# Amplifier.net
KiCad netlist of a schematic drawn in EAGLE
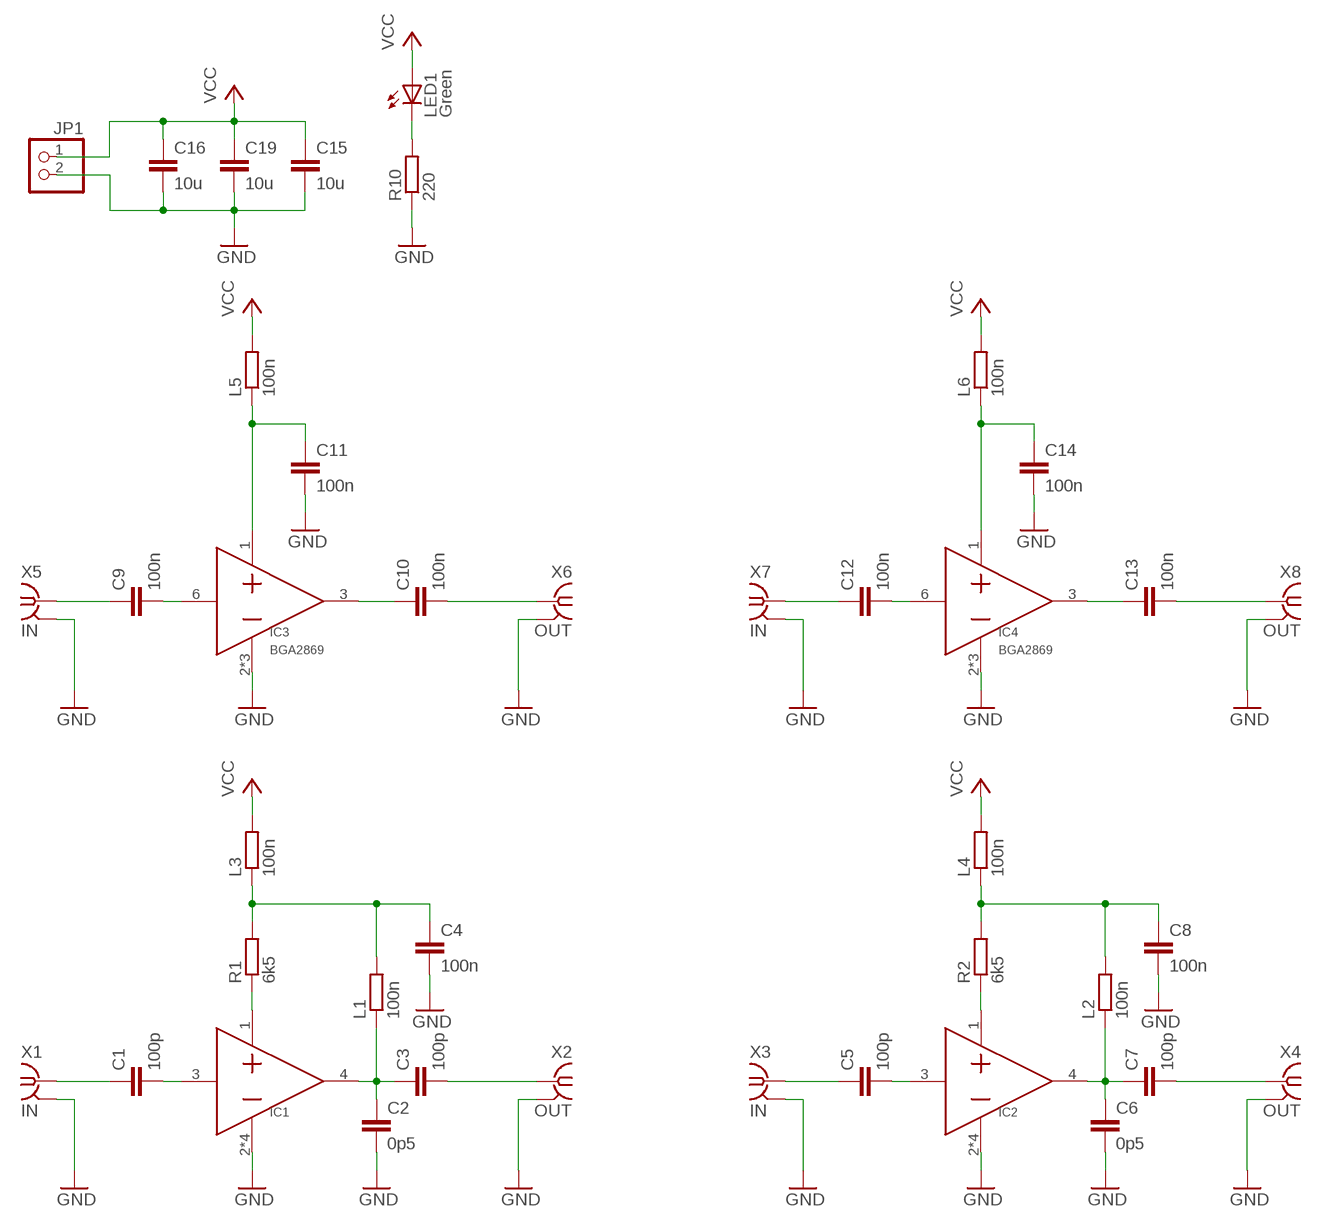
[diagram p0: schematic, sheet 1]

(export (version "E")
  (design (tool "Eeschema 10.0.6"))
  (components
    (comp (ref "C1")
      (value "100p")
      (footprint "eagle-import:C0603")
      (libsource (lib "eagle-import") (part "C-EUC0603"))
    )
    (comp (ref "C2")
      (value "0p5")
      (footprint "eagle-import:C0603")
      (libsource (lib "eagle-import") (part "C-EUC0603"))
    )
    (comp (ref "C3")
      (value "100p")
      (footprint "eagle-import:C0603")
      (libsource (lib "eagle-import") (part "C-EUC0603"))
    )
    (comp (ref "C4")
      (value "100n")
      (footprint "eagle-import:C0603")
      (libsource (lib "eagle-import") (part "C-EUC0603"))
    )
    (comp (ref "C5")
      (value "100p")
      (footprint "eagle-import:C0603")
      (libsource (lib "eagle-import") (part "C-EUC0603"))
    )
    (comp (ref "C6")
      (value "0p5")
      (footprint "eagle-import:C0603")
      (libsource (lib "eagle-import") (part "C-EUC0603"))
    )
    (comp (ref "C7")
      (value "100p")
      (footprint "eagle-import:C0603")
      (libsource (lib "eagle-import") (part "C-EUC0603"))
    )
    (comp (ref "C8")
      (value "100n")
      (footprint "eagle-import:C0603")
      (libsource (lib "eagle-import") (part "C-EUC0603"))
    )
    (comp (ref "C9")
      (value "100n")
      (footprint "eagle-import:C0603")
      (libsource (lib "eagle-import") (part "C-EUC0603"))
    )
    (comp (ref "C10")
      (value "100n")
      (footprint "eagle-import:C0603")
      (libsource (lib "eagle-import") (part "C-EUC0603"))
    )
    (comp (ref "C11")
      (value "100n")
      (footprint "eagle-import:C0603")
      (libsource (lib "eagle-import") (part "C-EUC0603"))
    )
    (comp (ref "C12")
      (value "100n")
      (footprint "eagle-import:C0603")
      (libsource (lib "eagle-import") (part "C-EUC0603"))
    )
    (comp (ref "C13")
      (value "100n")
      (footprint "eagle-import:C0603")
      (libsource (lib "eagle-import") (part "C-EUC0603"))
    )
    (comp (ref "C14")
      (value "100n")
      (footprint "eagle-import:C0603")
      (libsource (lib "eagle-import") (part "C-EUC0603"))
    )
    (comp (ref "C15")
      (value "10u")
      (footprint "eagle-import:C1206")
      (libsource (lib "eagle-import") (part "C-EUC1206"))
    )
    (comp (ref "C16")
      (value "10u")
      (footprint "eagle-import:C1206")
      (libsource (lib "eagle-import") (part "C-EUC1206"))
    )
    (comp (ref "C19")
      (value "10u")
      (footprint "eagle-import:C1206")
      (libsource (lib "eagle-import") (part "C-EUC1206"))
    )
    (comp (ref "IC1")
      (value "GRF4002")
      (footprint "eagle-import:SON50P150X150X45-7T60X110")
      (libsource (lib "eagle-import") (part "GRF4002"))
    )
    (comp (ref "IC2")
      (value "GRF4002")
      (footprint "eagle-import:SON50P150X150X45-7T60X110")
      (libsource (lib "eagle-import") (part "GRF4002"))
    )
    (comp (ref "IC3")
      (value "BGA2869")
      (footprint "eagle-import:SOT363")
      (libsource (lib "eagle-import") (part "BGA2869"))
    )
    (comp (ref "IC4")
      (value "BGA2869")
      (footprint "eagle-import:SOT363")
      (libsource (lib "eagle-import") (part "BGA2869"))
    )
    (comp (ref "JP1")
      (value "PINHD-1X2/90")
      (footprint "eagle-import:1X02_90")
      (libsource (lib "eagle-import") (part "PINHD-1X2/90"))
    )
    (comp (ref "L1")
      (value "100n")
      (footprint "eagle-import:R0603")
      (libsource (lib "eagle-import") (part "R-EU_R0603"))
    )
    (comp (ref "L2")
      (value "100n")
      (footprint "eagle-import:R0603")
      (libsource (lib "eagle-import") (part "R-EU_R0603"))
    )
    (comp (ref "L3")
      (value "100n")
      (footprint "eagle-import:R0603")
      (libsource (lib "eagle-import") (part "R-EU_R0603"))
    )
    (comp (ref "L4")
      (value "100n")
      (footprint "eagle-import:R0603")
      (libsource (lib "eagle-import") (part "R-EU_R0603"))
    )
    (comp (ref "L5")
      (value "100n")
      (footprint "eagle-import:R0603")
      (libsource (lib "eagle-import") (part "R-EU_R0603"))
    )
    (comp (ref "L6")
      (value "100n")
      (footprint "eagle-import:R0603")
      (libsource (lib "eagle-import") (part "R-EU_R0603"))
    )
    (comp (ref "LED1")
      (value "Green")
      (footprint "eagle-import:LED_SML0603")
      (libsource (lib "eagle-import") (part "LED_ESML0603"))
    )
    (comp (ref "R1")
      (value "6k5")
      (footprint "eagle-import:R0603")
      (libsource (lib "eagle-import") (part "R-EU_R0603"))
    )
    (comp (ref "R2")
      (value "6k5")
      (footprint "eagle-import:R0603")
      (libsource (lib "eagle-import") (part "R-EU_R0603"))
    )
    (comp (ref "R10")
      (value "220")
      (footprint "eagle-import:R0603")
      (libsource (lib "eagle-import") (part "R-EU_R0603"))
    )
    (comp (ref "X1")
      (value "IN")
      (footprint "eagle-import:J502-ND-142-0711-821_826")
      (libsource (lib "eagle-import") (part "SMA_CONNECTOR"))
    )
    (comp (ref "X2")
      (value "OUT")
      (footprint "eagle-import:J502-ND-142-0711-821_826")
      (libsource (lib "eagle-import") (part "SMA_CONNECTOR"))
    )
    (comp (ref "X3")
      (value "IN")
      (footprint "eagle-import:J502-ND-142-0711-821_826")
      (libsource (lib "eagle-import") (part "SMA_CONNECTOR"))
    )
    (comp (ref "X4")
      (value "OUT")
      (footprint "eagle-import:J502-ND-142-0711-821_826")
      (libsource (lib "eagle-import") (part "SMA_CONNECTOR"))
    )
    (comp (ref "X5")
      (value "IN")
      (footprint "eagle-import:J502-ND-142-0711-821_826")
      (libsource (lib "eagle-import") (part "SMA_CONNECTOR"))
    )
    (comp (ref "X6")
      (value "OUT")
      (footprint "eagle-import:J502-ND-142-0711-821_826")
      (libsource (lib "eagle-import") (part "SMA_CONNECTOR"))
    )
    (comp (ref "X7")
      (value "IN")
      (footprint "eagle-import:J502-ND-142-0711-821_826")
      (libsource (lib "eagle-import") (part "SMA_CONNECTOR"))
    )
    (comp (ref "X8")
      (value "OUT")
      (footprint "eagle-import:J502-ND-142-0711-821_826")
      (libsource (lib "eagle-import") (part "SMA_CONNECTOR"))
    )
  )
  (nets
    (net (code "1") (name "GND") (class "Default")
      (node (ref "C11") (pin "2") (pinfunction "2_2") (pintype "passive"))
      (node (ref "C14") (pin "2") (pinfunction "2_2") (pintype "passive"))
      (node (ref "C15") (pin "2") (pinfunction "2_2") (pintype "passive"))
      (node (ref "C16") (pin "2") (pinfunction "2_2") (pintype "passive"))
      (node (ref "C19") (pin "2") (pinfunction "2_2") (pintype "passive"))
      (node (ref "C2") (pin "2") (pinfunction "2_2") (pintype "passive"))
      (node (ref "C4") (pin "2") (pinfunction "2_2") (pintype "passive"))
      (node (ref "C6") (pin "2") (pinfunction "2_2") (pintype "passive"))
      (node (ref "C8") (pin "2") (pinfunction "2_2") (pintype "passive"))
      (node (ref "IC1") (pin "2") (pinfunction "GND_2") (pintype "bidirectional"))
      (node (ref "IC1") (pin "5") (pinfunction "GND_5") (pintype "bidirectional"))
      (node (ref "IC1") (pin "6") (pinfunction "GND_6") (pintype "bidirectional"))
      (node (ref "IC1") (pin "7") (pinfunction "GND_7") (pintype "bidirectional"))
      (node (ref "IC2") (pin "2") (pinfunction "GND_2") (pintype "bidirectional"))
      (node (ref "IC2") (pin "5") (pinfunction "GND_5") (pintype "bidirectional"))
      (node (ref "IC2") (pin "6") (pinfunction "GND_6") (pintype "bidirectional"))
      (node (ref "IC2") (pin "7") (pinfunction "GND_7") (pintype "bidirectional"))
      (node (ref "IC3") (pin "2") (pinfunction "GND_2") (pintype "bidirectional"))
      (node (ref "IC3") (pin "4") (pinfunction "GND_4") (pintype "bidirectional"))
      (node (ref "IC3") (pin "5") (pinfunction "GND_5") (pintype "bidirectional"))
      (node (ref "IC4") (pin "2") (pinfunction "GND_2") (pintype "bidirectional"))
      (node (ref "IC4") (pin "4") (pinfunction "GND_4") (pintype "bidirectional"))
      (node (ref "IC4") (pin "5") (pinfunction "GND_5") (pintype "bidirectional"))
      (node (ref "JP1") (pin "2") (pinfunction "2_2") (pintype "passive"))
      (node (ref "R10") (pin "1") (pinfunction "1_1") (pintype "passive"))
      (node (ref "X1") (pin "G@1") (pinfunction "2_G@1") (pintype "passive"))
      (node (ref "X1") (pin "G@2") (pinfunction "2_G@2") (pintype "passive"))
      (node (ref "X1") (pin "G@3") (pinfunction "2_G@3") (pintype "passive"))
      (node (ref "X1") (pin "G@4") (pinfunction "2_G@4") (pintype "passive"))
      (node (ref "X2") (pin "G@1") (pinfunction "2_G@1") (pintype "passive"))
      (node (ref "X2") (pin "G@2") (pinfunction "2_G@2") (pintype "passive"))
      (node (ref "X2") (pin "G@3") (pinfunction "2_G@3") (pintype "passive"))
      (node (ref "X2") (pin "G@4") (pinfunction "2_G@4") (pintype "passive"))
      (node (ref "X3") (pin "G@1") (pinfunction "2_G@1") (pintype "passive"))
      (node (ref "X3") (pin "G@2") (pinfunction "2_G@2") (pintype "passive"))
      (node (ref "X3") (pin "G@3") (pinfunction "2_G@3") (pintype "passive"))
      (node (ref "X3") (pin "G@4") (pinfunction "2_G@4") (pintype "passive"))
      (node (ref "X4") (pin "G@1") (pinfunction "2_G@1") (pintype "passive"))
      (node (ref "X4") (pin "G@2") (pinfunction "2_G@2") (pintype "passive"))
      (node (ref "X4") (pin "G@3") (pinfunction "2_G@3") (pintype "passive"))
      (node (ref "X4") (pin "G@4") (pinfunction "2_G@4") (pintype "passive"))
      (node (ref "X5") (pin "G@1") (pinfunction "2_G@1") (pintype "passive"))
      (node (ref "X5") (pin "G@2") (pinfunction "2_G@2") (pintype "passive"))
      (node (ref "X5") (pin "G@3") (pinfunction "2_G@3") (pintype "passive"))
      (node (ref "X5") (pin "G@4") (pinfunction "2_G@4") (pintype "passive"))
      (node (ref "X6") (pin "G@1") (pinfunction "2_G@1") (pintype "passive"))
      (node (ref "X6") (pin "G@2") (pinfunction "2_G@2") (pintype "passive"))
      (node (ref "X6") (pin "G@3") (pinfunction "2_G@3") (pintype "passive"))
      (node (ref "X6") (pin "G@4") (pinfunction "2_G@4") (pintype "passive"))
      (node (ref "X7") (pin "G@1") (pinfunction "2_G@1") (pintype "passive"))
      (node (ref "X7") (pin "G@2") (pinfunction "2_G@2") (pintype "passive"))
      (node (ref "X7") (pin "G@3") (pinfunction "2_G@3") (pintype "passive"))
      (node (ref "X7") (pin "G@4") (pinfunction "2_G@4") (pintype "passive"))
      (node (ref "X8") (pin "G@1") (pinfunction "2_G@1") (pintype "passive"))
      (node (ref "X8") (pin "G@2") (pinfunction "2_G@2") (pintype "passive"))
      (node (ref "X8") (pin "G@3") (pinfunction "2_G@3") (pintype "passive"))
      (node (ref "X8") (pin "G@4") (pinfunction "2_G@4") (pintype "passive"))
    )
    (net (code "2") (name "Net-(C1-Pad1)") (class "Default")
      (node (ref "C1") (pin "1") (pinfunction "1_1") (pintype "passive"))
      (node (ref "X1") (pin "1") (pinfunction "1_1") (pintype "passive"))
    )
    (net (code "3") (name "Net-(C3-Pad2)") (class "Default")
      (node (ref "C3") (pin "2") (pinfunction "2_2") (pintype "passive"))
      (node (ref "X2") (pin "1") (pinfunction "1_1") (pintype "passive"))
    )
    (net (code "4") (name "Net-(C4-Pad1)") (class "Default")
      (node (ref "C4") (pin "1") (pinfunction "1_1") (pintype "passive"))
      (node (ref "L1") (pin "2") (pinfunction "2_2") (pintype "passive"))
      (node (ref "L3") (pin "1") (pinfunction "1_1") (pintype "passive"))
      (node (ref "R1") (pin "2") (pinfunction "2_2") (pintype "passive"))
    )
    (net (code "5") (name "Net-(C5-Pad1)") (class "Default")
      (node (ref "C5") (pin "1") (pinfunction "1_1") (pintype "passive"))
      (node (ref "X3") (pin "1") (pinfunction "1_1") (pintype "passive"))
    )
    (net (code "6") (name "Net-(C7-Pad2)") (class "Default")
      (node (ref "C7") (pin "2") (pinfunction "2_2") (pintype "passive"))
      (node (ref "X4") (pin "1") (pinfunction "1_1") (pintype "passive"))
    )
    (net (code "7") (name "Net-(C8-Pad1)") (class "Default")
      (node (ref "C8") (pin "1") (pinfunction "1_1") (pintype "passive"))
      (node (ref "L2") (pin "2") (pinfunction "2_2") (pintype "passive"))
      (node (ref "L4") (pin "1") (pinfunction "1_1") (pintype "passive"))
      (node (ref "R2") (pin "2") (pinfunction "2_2") (pintype "passive"))
    )
    (net (code "8") (name "Net-(C9-Pad1)") (class "Default")
      (node (ref "C9") (pin "1") (pinfunction "1_1") (pintype "passive"))
      (node (ref "X5") (pin "1") (pinfunction "1_1") (pintype "passive"))
    )
    (net (code "9") (name "Net-(C10-Pad2)") (class "Default")
      (node (ref "C10") (pin "2") (pinfunction "2_2") (pintype "passive"))
      (node (ref "X6") (pin "1") (pinfunction "1_1") (pintype "passive"))
    )
    (net (code "10") (name "Net-(C12-Pad1)") (class "Default")
      (node (ref "C12") (pin "1") (pinfunction "1_1") (pintype "passive"))
      (node (ref "X7") (pin "1") (pinfunction "1_1") (pintype "passive"))
    )
    (net (code "11") (name "Net-(C13-Pad2)") (class "Default")
      (node (ref "C13") (pin "2") (pinfunction "2_2") (pintype "passive"))
      (node (ref "X8") (pin "1") (pinfunction "1_1") (pintype "passive"))
    )
    (net (code "12") (name "Net-(IC1-IN)") (class "Default")
      (node (ref "C1") (pin "2") (pinfunction "2_2") (pintype "passive"))
      (node (ref "IC1") (pin "3") (pinfunction "IN_3") (pintype "bidirectional"))
    )
    (net (code "13") (name "Net-(IC1-OUT)") (class "Default")
      (node (ref "C2") (pin "1") (pinfunction "1_1") (pintype "passive"))
      (node (ref "C3") (pin "1") (pinfunction "1_1") (pintype "passive"))
      (node (ref "IC1") (pin "4") (pinfunction "OUT_4") (pintype "bidirectional"))
      (node (ref "L1") (pin "1") (pinfunction "1_1") (pintype "passive"))
    )
    (net (code "14") (name "Net-(IC1-VCC)") (class "Default")
      (node (ref "IC1") (pin "1") (pinfunction "VCC_1") (pintype "bidirectional"))
      (node (ref "R1") (pin "1") (pinfunction "1_1") (pintype "passive"))
    )
    (net (code "15") (name "Net-(IC2-IN)") (class "Default")
      (node (ref "C5") (pin "2") (pinfunction "2_2") (pintype "passive"))
      (node (ref "IC2") (pin "3") (pinfunction "IN_3") (pintype "bidirectional"))
    )
    (net (code "16") (name "Net-(IC2-OUT)") (class "Default")
      (node (ref "C6") (pin "1") (pinfunction "1_1") (pintype "passive"))
      (node (ref "C7") (pin "1") (pinfunction "1_1") (pintype "passive"))
      (node (ref "IC2") (pin "4") (pinfunction "OUT_4") (pintype "bidirectional"))
      (node (ref "L2") (pin "1") (pinfunction "1_1") (pintype "passive"))
    )
    (net (code "17") (name "Net-(IC2-VCC)") (class "Default")
      (node (ref "IC2") (pin "1") (pinfunction "VCC_1") (pintype "bidirectional"))
      (node (ref "R2") (pin "1") (pinfunction "1_1") (pintype "passive"))
    )
    (net (code "18") (name "Net-(IC3-IN)") (class "Default")
      (node (ref "C9") (pin "2") (pinfunction "2_2") (pintype "passive"))
      (node (ref "IC3") (pin "6") (pinfunction "IN_6") (pintype "bidirectional"))
    )
    (net (code "19") (name "Net-(IC3-OUT)") (class "Default")
      (node (ref "C10") (pin "1") (pinfunction "1_1") (pintype "passive"))
      (node (ref "IC3") (pin "3") (pinfunction "OUT_3") (pintype "bidirectional"))
    )
    (net (code "20") (name "Net-(IC3-VCC)") (class "Default")
      (node (ref "C11") (pin "1") (pinfunction "1_1") (pintype "passive"))
      (node (ref "IC3") (pin "1") (pinfunction "VCC_1") (pintype "bidirectional"))
      (node (ref "L5") (pin "1") (pinfunction "1_1") (pintype "passive"))
    )
    (net (code "21") (name "Net-(IC4-IN)") (class "Default")
      (node (ref "C12") (pin "2") (pinfunction "2_2") (pintype "passive"))
      (node (ref "IC4") (pin "6") (pinfunction "IN_6") (pintype "bidirectional"))
    )
    (net (code "22") (name "Net-(IC4-OUT)") (class "Default")
      (node (ref "C13") (pin "1") (pinfunction "1_1") (pintype "passive"))
      (node (ref "IC4") (pin "3") (pinfunction "OUT_3") (pintype "bidirectional"))
    )
    (net (code "23") (name "Net-(IC4-VCC)") (class "Default")
      (node (ref "C14") (pin "1") (pinfunction "1_1") (pintype "passive"))
      (node (ref "IC4") (pin "1") (pinfunction "VCC_1") (pintype "bidirectional"))
      (node (ref "L6") (pin "1") (pinfunction "1_1") (pintype "passive"))
    )
    (net (code "24") (name "Net-(LED1-PadC)") (class "Default")
      (node (ref "LED1") (pin "C") (pinfunction "C_C") (pintype "passive"))
      (node (ref "R10") (pin "2") (pinfunction "2_2") (pintype "passive"))
    )
    (net (code "25") (name "VCC") (class "Default")
      (node (ref "C15") (pin "1") (pinfunction "1_1") (pintype "passive"))
      (node (ref "C16") (pin "1") (pinfunction "1_1") (pintype "passive"))
      (node (ref "C19") (pin "1") (pinfunction "1_1") (pintype "passive"))
      (node (ref "JP1") (pin "1") (pinfunction "1_1") (pintype "passive"))
      (node (ref "L3") (pin "2") (pinfunction "2_2") (pintype "passive"))
      (node (ref "L4") (pin "2") (pinfunction "2_2") (pintype "passive"))
      (node (ref "L5") (pin "2") (pinfunction "2_2") (pintype "passive"))
      (node (ref "L6") (pin "2") (pinfunction "2_2") (pintype "passive"))
      (node (ref "LED1") (pin "A") (pinfunction "A_A") (pintype "passive"))
    )
  )
)
